# ps2_to_db9_double.net
KiCad netlist of a schematic drawn in EAGLE
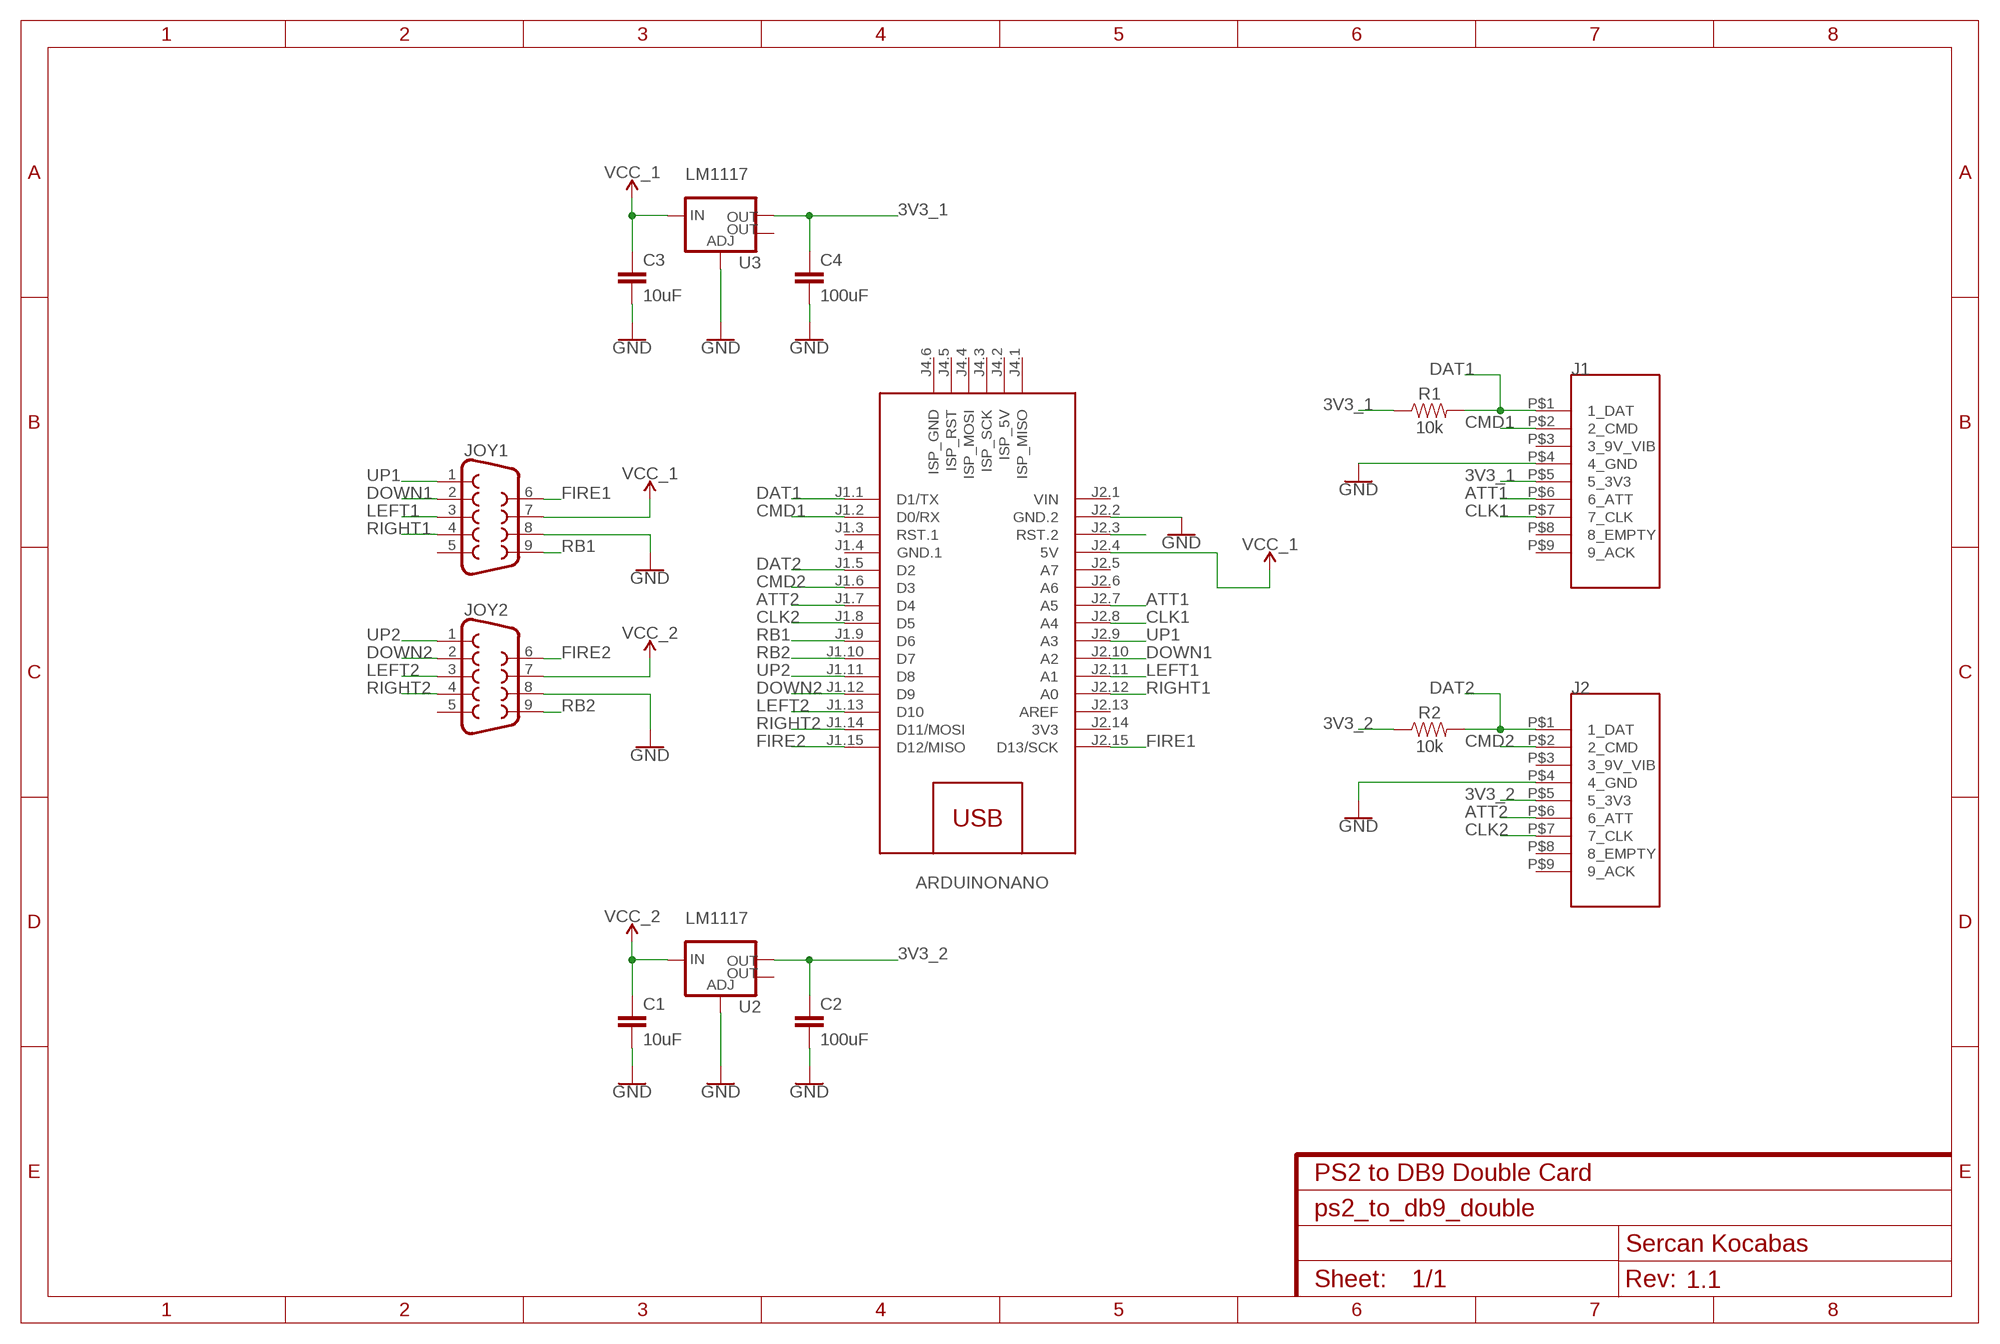
[diagram p0: schematic, sheet 1]

(export (version "E")
  (design (tool "Eeschema 10.0.6"))
  (components
    (comp (ref "ARDUINONANO")
      (value "ARDUINO-NANO-3.0#ISP")
      (footprint "eagle-import:ARDUINO-NANO-3.0#ISP")
      (libsource (lib "eagle-import") (part "ARDUINO-NANO-3.0#ISP"))
    )
    (comp (ref "C1")
      (value "10uF")
      (footprint "eagle-import:C025-025X050")
      (libsource (lib "eagle-import") (part "C-EU025-025X050"))
    )
    (comp (ref "C2")
      (value "100uF")
      (footprint "eagle-import:C025-025X050")
      (libsource (lib "eagle-import") (part "C-EU025-025X050"))
    )
    (comp (ref "C3")
      (value "10uF")
      (footprint "eagle-import:C025-025X050")
      (libsource (lib "eagle-import") (part "C-EU025-025X050"))
    )
    (comp (ref "C4")
      (value "100uF")
      (footprint "eagle-import:C025-025X050")
      (libsource (lib "eagle-import") (part "C-EU025-025X050"))
    )
    (comp (ref "J1")
      (value "PS2_DUALSHOCK_UP")
      (footprint "eagle-import:PS2_DUALSHOCK_UP")
      (libsource (lib "eagle-import") (part "PS2_DUALSHOCK_UP"))
    )
    (comp (ref "J2")
      (value "PS2_DUALSHOCK_UP")
      (footprint "eagle-import:PS2_DUALSHOCK_UP")
      (libsource (lib "eagle-import") (part "PS2_DUALSHOCK_UP"))
    )
    (comp (ref "JOY1")
      (value "DB9FEMALE")
      (footprint "eagle-import:DB9")
      (libsource (lib "eagle-import") (part "DB9FEMALE"))
    )
    (comp (ref "JOY2")
      (value "DB9FEMALE")
      (footprint "eagle-import:DB9")
      (libsource (lib "eagle-import") (part "DB9FEMALE"))
    )
    (comp (ref "R1")
      (value "10k")
      (footprint "eagle-import:AXIAL-0.3")
      (libsource (lib "eagle-import") (part "10OHM-HORIZ-1/4W-1%"))
    )
    (comp (ref "R2")
      (value "10k")
      (footprint "eagle-import:AXIAL-0.3")
      (libsource (lib "eagle-import") (part "10OHM-HORIZ-1/4W-1%"))
    )
    (comp (ref "U2")
      (value "LM1117")
      (footprint "eagle-import:SOT223")
      (libsource (lib "eagle-import") (part "V_REG_LM1117SOT223"))
    )
    (comp (ref "U3")
      (value "LM1117")
      (footprint "eagle-import:SOT223")
      (libsource (lib "eagle-import") (part "V_REG_LM1117SOT223"))
    )
  )
  (nets
    (net (code "1") (name "/3V3") (class "Default")
      (node (ref "ARDUINONANO") (pin "J2.14") (pinfunction "3V3_J2.14") (pintype "power_in"))
    )
    (net (code "2") (name "/3V3_1") (class "Default")
      (node (ref "C4") (pin "1") (pinfunction "1_1") (pintype "passive"))
      (node (ref "J1") (pin "P$5") (pinfunction "5_3V3_P$5") (pintype "bidirectional"))
      (node (ref "R1") (pin "P$1") (pinfunction "1_P$1") (pintype "passive"))
      (node (ref "U3") (pin "2") (pinfunction "OUT_2") (pintype "output"))
    )
    (net (code "3") (name "/3V3_2") (class "Default")
      (node (ref "C2") (pin "1") (pinfunction "1_1") (pintype "passive"))
      (node (ref "J2") (pin "P$5") (pinfunction "5_3V3_P$5") (pintype "bidirectional"))
      (node (ref "R2") (pin "P$1") (pinfunction "1_P$1") (pintype "passive"))
      (node (ref "U2") (pin "2") (pinfunction "OUT_2") (pintype "output"))
    )
    (net (code "4") (name "/ATT1") (class "Default")
      (node (ref "ARDUINONANO") (pin "J2.7") (pinfunction "A5_J2.7") (pintype "bidirectional"))
      (node (ref "J1") (pin "P$6") (pinfunction "6_ATT_P$6") (pintype "bidirectional"))
    )
    (net (code "5") (name "/ATT2") (class "Default")
      (node (ref "ARDUINONANO") (pin "J1.7") (pinfunction "D4_J1.7") (pintype "bidirectional"))
      (node (ref "J2") (pin "P$6") (pinfunction "6_ATT_P$6") (pintype "bidirectional"))
    )
    (net (code "6") (name "/CLK1") (class "Default")
      (node (ref "ARDUINONANO") (pin "J2.8") (pinfunction "A4_J2.8") (pintype "bidirectional"))
      (node (ref "J1") (pin "P$7") (pinfunction "7_CLK_P$7") (pintype "bidirectional"))
    )
    (net (code "7") (name "/CLK2") (class "Default")
      (node (ref "ARDUINONANO") (pin "J1.8") (pinfunction "D5_J1.8") (pintype "bidirectional"))
      (node (ref "J2") (pin "P$7") (pinfunction "7_CLK_P$7") (pintype "bidirectional"))
    )
    (net (code "8") (name "/CMD1") (class "Default")
      (node (ref "ARDUINONANO") (pin "J1.2") (pinfunction "D0/RX_J1.2") (pintype "bidirectional"))
      (node (ref "J1") (pin "P$2") (pinfunction "2_CMD_P$2") (pintype "bidirectional"))
    )
    (net (code "9") (name "/CMD2") (class "Default")
      (node (ref "ARDUINONANO") (pin "J1.6") (pinfunction "D3_J1.6") (pintype "bidirectional"))
      (node (ref "J2") (pin "P$2") (pinfunction "2_CMD_P$2") (pintype "bidirectional"))
    )
    (net (code "10") (name "/DAT1") (class "Default")
      (node (ref "ARDUINONANO") (pin "J1.1") (pinfunction "D1/TX_J1.1") (pintype "bidirectional"))
      (node (ref "J1") (pin "P$1") (pinfunction "1_DAT_P$1") (pintype "bidirectional"))
      (node (ref "R1") (pin "P$2") (pinfunction "2_P$2") (pintype "passive"))
    )
    (net (code "11") (name "/DAT2") (class "Default")
      (node (ref "ARDUINONANO") (pin "J1.5") (pinfunction "D2_J1.5") (pintype "bidirectional"))
      (node (ref "J2") (pin "P$1") (pinfunction "1_DAT_P$1") (pintype "bidirectional"))
      (node (ref "R2") (pin "P$2") (pinfunction "2_P$2") (pintype "passive"))
    )
    (net (code "12") (name "/DOWN1") (class "Default")
      (node (ref "ARDUINONANO") (pin "J2.10") (pinfunction "A2_J2.10") (pintype "bidirectional"))
      (node (ref "JOY1") (pin "2") (pinfunction "2_2") (pintype "passive"))
    )
    (net (code "13") (name "/DOWN2") (class "Default")
      (node (ref "ARDUINONANO") (pin "J1.12") (pinfunction "D9_J1.12") (pintype "bidirectional"))
      (node (ref "JOY2") (pin "2") (pinfunction "2_2") (pintype "passive"))
    )
    (net (code "14") (name "/FIRE1") (class "Default")
      (node (ref "ARDUINONANO") (pin "J2.15") (pinfunction "D13/SCK_J2.15") (pintype "bidirectional"))
      (node (ref "JOY1") (pin "6") (pinfunction "6_6") (pintype "passive"))
    )
    (net (code "15") (name "/FIRE2") (class "Default")
      (node (ref "ARDUINONANO") (pin "J1.15") (pinfunction "D12/MISO_J1.15") (pintype "bidirectional"))
      (node (ref "JOY2") (pin "6") (pinfunction "6_6") (pintype "passive"))
    )
    (net (code "16") (name "/GND.1") (class "Default")
      (node (ref "ARDUINONANO") (pin "J1.4") (pinfunction "GND.1_J1.4") (pintype "power_in"))
    )
    (net (code "17") (name "/LEFT1") (class "Default")
      (node (ref "ARDUINONANO") (pin "J2.11") (pinfunction "A1_J2.11") (pintype "bidirectional"))
      (node (ref "JOY1") (pin "3") (pinfunction "3_3") (pintype "passive"))
    )
    (net (code "18") (name "/LEFT2") (class "Default")
      (node (ref "ARDUINONANO") (pin "J1.13") (pinfunction "D10_J1.13") (pintype "bidirectional"))
      (node (ref "JOY2") (pin "3") (pinfunction "3_3") (pintype "passive"))
    )
    (net (code "19") (name "/RB1") (class "Default")
      (node (ref "ARDUINONANO") (pin "J1.9") (pinfunction "D6_J1.9") (pintype "bidirectional"))
      (node (ref "JOY1") (pin "9") (pinfunction "9_9") (pintype "passive"))
    )
    (net (code "20") (name "/RB2") (class "Default")
      (node (ref "ARDUINONANO") (pin "J1.10") (pinfunction "D7_J1.10") (pintype "bidirectional"))
      (node (ref "JOY2") (pin "9") (pinfunction "9_9") (pintype "passive"))
    )
    (net (code "21") (name "/RIGHT1") (class "Default")
      (node (ref "ARDUINONANO") (pin "J2.12") (pinfunction "A0_J2.12") (pintype "bidirectional"))
      (node (ref "JOY1") (pin "4") (pinfunction "4_4") (pintype "passive"))
    )
    (net (code "22") (name "/RIGHT2") (class "Default")
      (node (ref "ARDUINONANO") (pin "J1.14") (pinfunction "D11/MOSI_J1.14") (pintype "bidirectional"))
      (node (ref "JOY2") (pin "4") (pinfunction "4_4") (pintype "passive"))
    )
    (net (code "23") (name "/UP1") (class "Default")
      (node (ref "ARDUINONANO") (pin "J2.9") (pinfunction "A3_J2.9") (pintype "bidirectional"))
      (node (ref "JOY1") (pin "1") (pinfunction "1_1") (pintype "passive"))
    )
    (net (code "24") (name "/UP2") (class "Default")
      (node (ref "ARDUINONANO") (pin "J1.11") (pinfunction "D8_J1.11") (pintype "bidirectional"))
      (node (ref "JOY2") (pin "1") (pinfunction "1_1") (pintype "passive"))
    )
    (net (code "25") (name "/VIN") (class "Default")
      (node (ref "ARDUINONANO") (pin "J2.1") (pinfunction "VIN_J2.1") (pintype "power_in"))
    )
    (net (code "26") (name "GND") (class "Default")
      (node (ref "ARDUINONANO") (pin "J2.2") (pinfunction "GND.2_J2.2") (pintype "power_in"))
      (node (ref "C1") (pin "2") (pinfunction "2_2") (pintype "passive"))
      (node (ref "C2") (pin "2") (pinfunction "2_2") (pintype "passive"))
      (node (ref "C3") (pin "2") (pinfunction "2_2") (pintype "passive"))
      (node (ref "C4") (pin "2") (pinfunction "2_2") (pintype "passive"))
      (node (ref "J1") (pin "P$4") (pinfunction "4_GND_P$4") (pintype "bidirectional"))
      (node (ref "J2") (pin "P$4") (pinfunction "4_GND_P$4") (pintype "bidirectional"))
      (node (ref "JOY1") (pin "8") (pinfunction "8_8") (pintype "passive"))
      (node (ref "JOY2") (pin "8") (pinfunction "8_8") (pintype "passive"))
      (node (ref "U2") (pin "1") (pinfunction "ADJ_1") (pintype "input"))
      (node (ref "U3") (pin "1") (pinfunction "ADJ_1") (pintype "input"))
    )
    (net (code "27") (name "VCC_1") (class "Default")
      (node (ref "ARDUINONANO") (pin "J2.4") (pinfunction "5V_J2.4") (pintype "power_in"))
      (node (ref "C3") (pin "1") (pinfunction "1_1") (pintype "passive"))
      (node (ref "JOY1") (pin "7") (pinfunction "7_7") (pintype "passive"))
      (node (ref "U3") (pin "3") (pinfunction "IN_3") (pintype "input"))
    )
    (net (code "28") (name "VCC_2") (class "Default")
      (node (ref "C1") (pin "1") (pinfunction "1_1") (pintype "passive"))
      (node (ref "JOY2") (pin "7") (pinfunction "7_7") (pintype "passive"))
      (node (ref "U2") (pin "3") (pinfunction "IN_3") (pintype "input"))
    )
    (net (code "29") (name "unconnected-(ARDUINONANO-A6-PadJ2.6)") (class "Default")
      (node (ref "ARDUINONANO") (pin "J2.6") (pinfunction "A6_J2.6") (pintype "bidirectional"))
    )
    (net (code "30") (name "unconnected-(ARDUINONANO-A7-PadJ2.5)") (class "Default")
      (node (ref "ARDUINONANO") (pin "J2.5") (pinfunction "A7_J2.5") (pintype "bidirectional"))
    )
    (net (code "31") (name "unconnected-(ARDUINONANO-AREF-PadJ2.13)") (class "Default")
      (node (ref "ARDUINONANO") (pin "J2.13") (pinfunction "AREF_J2.13") (pintype "bidirectional"))
    )
    (net (code "32") (name "unconnected-(ARDUINONANO-ISP_5V-PadJ4.2)") (class "Default")
      (node (ref "ARDUINONANO") (pin "J4.2") (pinfunction "ISP_5V_J4.2") (pintype "bidirectional"))
    )
    (net (code "33") (name "unconnected-(ARDUINONANO-ISP_GND-PadJ4.6)") (class "Default")
      (node (ref "ARDUINONANO") (pin "J4.6") (pinfunction "ISP_GND_J4.6") (pintype "bidirectional"))
    )
    (net (code "34") (name "unconnected-(ARDUINONANO-ISP_MISO-PadJ4.1)") (class "Default")
      (node (ref "ARDUINONANO") (pin "J4.1") (pinfunction "ISP_MISO_J4.1") (pintype "bidirectional"))
    )
    (net (code "35") (name "unconnected-(ARDUINONANO-ISP_MOSI-PadJ4.4)") (class "Default")
      (node (ref "ARDUINONANO") (pin "J4.4") (pinfunction "ISP_MOSI_J4.4") (pintype "bidirectional"))
    )
    (net (code "36") (name "unconnected-(ARDUINONANO-ISP_RST-PadJ4.5)") (class "Default")
      (node (ref "ARDUINONANO") (pin "J4.5") (pinfunction "ISP_RST_J4.5") (pintype "bidirectional"))
    )
    (net (code "37") (name "unconnected-(ARDUINONANO-ISP_SCK-PadJ4.3)") (class "Default")
      (node (ref "ARDUINONANO") (pin "J4.3") (pinfunction "ISP_SCK_J4.3") (pintype "bidirectional"))
    )
    (net (code "38") (name "unconnected-(ARDUINONANO-RST.1-PadJ1.3)") (class "Default")
      (node (ref "ARDUINONANO") (pin "J1.3") (pinfunction "RST.1_J1.3") (pintype "bidirectional"))
    )
    (net (code "39") (name "unconnected-(ARDUINONANO-RST.2-PadJ2.3)") (class "Default")
      (node (ref "ARDUINONANO") (pin "J2.3") (pinfunction "RST.2_J2.3") (pintype "bidirectional"))
    )
    (net (code "40") (name "unconnected-(J1-3_9V_VIB-PadP$3)") (class "Default")
      (node (ref "J1") (pin "P$3") (pinfunction "3_9V_VIB_P$3") (pintype "bidirectional"))
    )
    (net (code "41") (name "unconnected-(J1-8_EMPTY-PadP$8)") (class "Default")
      (node (ref "J1") (pin "P$8") (pinfunction "8_EMPTY_P$8") (pintype "bidirectional"))
    )
    (net (code "42") (name "unconnected-(J1-9_ACK-PadP$9)") (class "Default")
      (node (ref "J1") (pin "P$9") (pinfunction "9_ACK_P$9") (pintype "bidirectional"))
    )
    (net (code "43") (name "unconnected-(J2-3_9V_VIB-PadP$3)") (class "Default")
      (node (ref "J2") (pin "P$3") (pinfunction "3_9V_VIB_P$3") (pintype "bidirectional"))
    )
    (net (code "44") (name "unconnected-(J2-8_EMPTY-PadP$8)") (class "Default")
      (node (ref "J2") (pin "P$8") (pinfunction "8_EMPTY_P$8") (pintype "bidirectional"))
    )
    (net (code "45") (name "unconnected-(J2-9_ACK-PadP$9)") (class "Default")
      (node (ref "J2") (pin "P$9") (pinfunction "9_ACK_P$9") (pintype "bidirectional"))
    )
    (net (code "46") (name "unconnected-(JOY1-Pad5)") (class "Default")
      (node (ref "JOY1") (pin "5") (pinfunction "5_5") (pintype "passive"))
    )
    (net (code "47") (name "unconnected-(JOY2-Pad5)") (class "Default")
      (node (ref "JOY2") (pin "5") (pinfunction "5_5") (pintype "passive"))
    )
    (net (code "48") (name "unconnected-(U2-OUT-Pad4)") (class "Default")
      (node (ref "U2") (pin "4") (pinfunction "OUT_4") (pintype "output"))
    )
    (net (code "49") (name "unconnected-(U3-OUT-Pad4)") (class "Default")
      (node (ref "U3") (pin "4") (pinfunction "OUT_4") (pintype "output"))
    )
  )
)
